# QUTMS-TSAL-V00-S00.net
KiCad netlist of a schematic drawn in Altium Designer
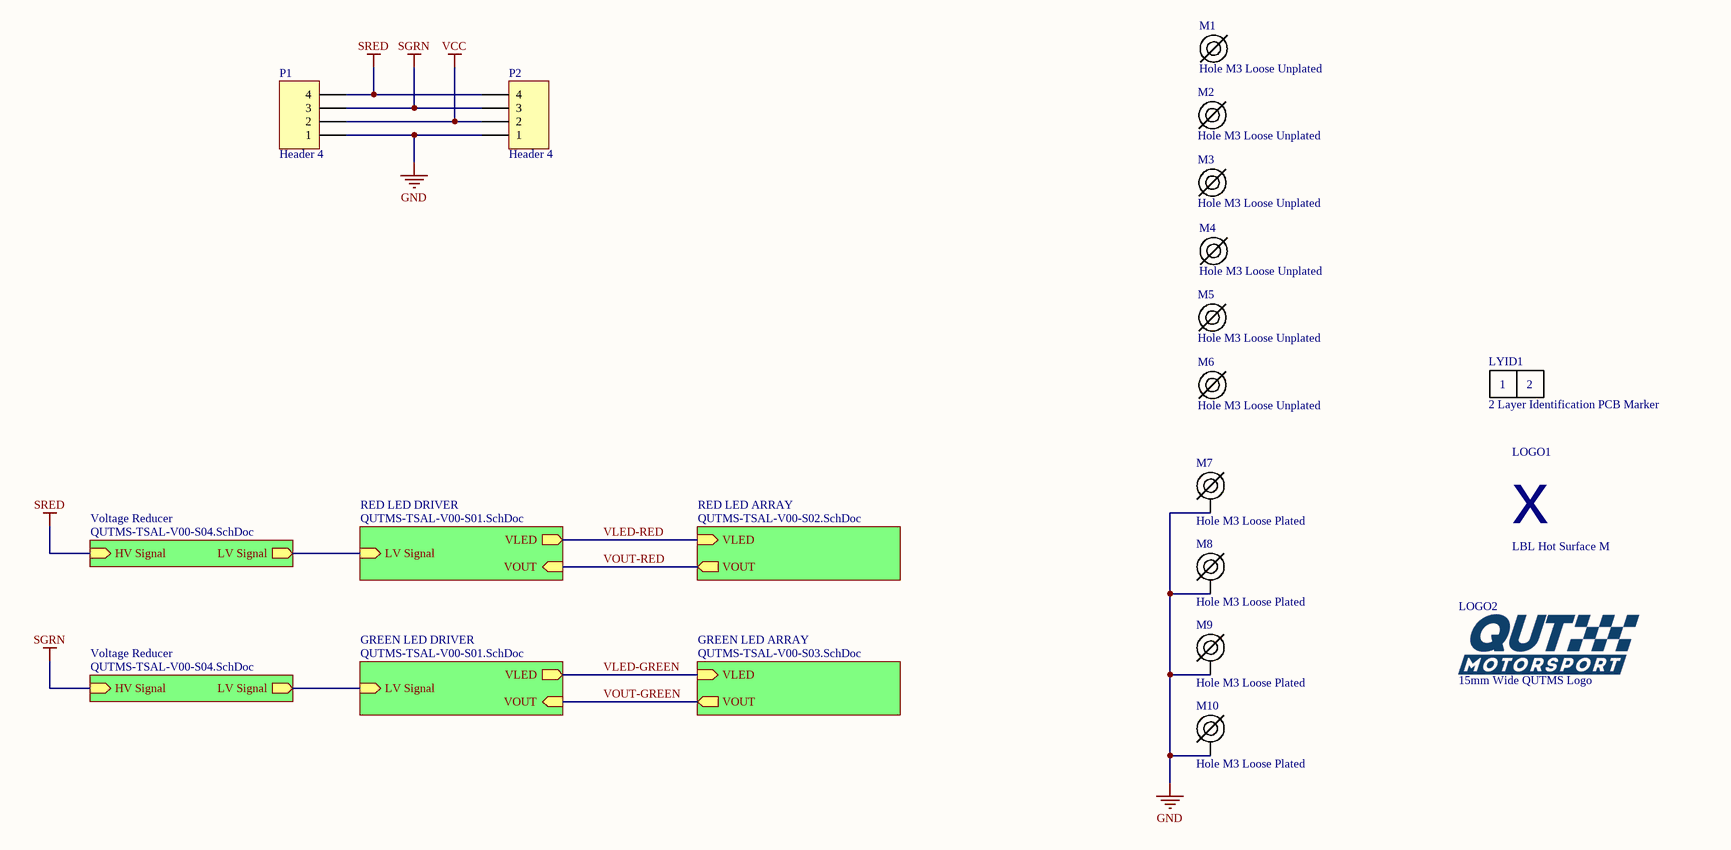
[diagram p0: QUTMS-TSAL-V00-S00.SchDoc]

(export (version "E")
  (design (tool "Eeschema 10.0.6"))
  (components
    (comp (ref "LOGO1")
      (value "LBL Hot Surface M")
      (footprint "LBL HOT MEDIUM")
      (libsource (lib "QUTMS_PCBLibrary") (part "LBL Hot Surface M"))
    )
    (comp (ref "LOGO2")
      (value "15mm Wide QUTMS Logo")
      (footprint "QUTMS LOGO 15MM")
      (libsource (lib "QUTMS_PCBLibrary") (part "QUTMS Logo 15mm"))
    )
    (comp (ref "LYID1")
      (value "2 Layer Identification PCB Marker")
      (footprint "LAYER IDENT 2")
      (libsource (lib "QUTMS_PCBLibrary") (part "Layer Identification 2"))
    )
    (comp (ref "M1")
      (value "Hole M3 Loose Unplated")
      (footprint "M3.5 UNPLATED")
      (description "M3.5 Hole, No Plating")
      (libsource (lib "QUTMS_PCBLibrary") (part "Hole M3 Loose Unplated"))
    )
    (comp (ref "M2")
      (value "Hole M3 Loose Unplated")
      (footprint "M3.5 UNPLATED")
      (description "M3.5 Hole, No Plating")
      (libsource (lib "QUTMS_PCBLibrary") (part "Hole M3 Loose Unplated"))
    )
    (comp (ref "M3")
      (value "Hole M3 Loose Unplated")
      (footprint "M3.5 UNPLATED")
      (description "M3.5 Hole, No Plating")
      (libsource (lib "QUTMS_PCBLibrary") (part "Hole M3 Loose Unplated"))
    )
    (comp (ref "M4")
      (value "Hole M3 Loose Unplated")
      (footprint "M3.5 UNPLATED")
      (description "M3.5 Hole, No Plating")
      (libsource (lib "QUTMS_PCBLibrary") (part "Hole M3 Loose Unplated"))
    )
    (comp (ref "M5")
      (value "Hole M3 Loose Unplated")
      (footprint "M3.5 UNPLATED")
      (description "M3.5 Hole, No Plating")
      (libsource (lib "QUTMS_PCBLibrary") (part "Hole M3 Loose Unplated"))
    )
    (comp (ref "M6")
      (value "Hole M3 Loose Unplated")
      (footprint "M3.5 UNPLATED")
      (description "M3.5 Hole, No Plating")
      (libsource (lib "QUTMS_PCBLibrary") (part "Hole M3 Loose Unplated"))
    )
    (comp (ref "M7")
      (value "Hole M3 Loose Plated")
      (footprint "M3.5 PLATED")
      (description "M3.5 Hole, Plated")
      (libsource (lib "QUTMS_PCBLibrary") (part "Hole M3 Loose Plated"))
    )
    (comp (ref "M8")
      (value "Hole M3 Loose Plated")
      (footprint "M3.5 PLATED")
      (description "M3.5 Hole, Plated")
      (libsource (lib "QUTMS_PCBLibrary") (part "Hole M3 Loose Plated"))
    )
    (comp (ref "M9")
      (value "Hole M3 Loose Plated")
      (footprint "M3.5 PLATED")
      (description "M3.5 Hole, Plated")
      (libsource (lib "QUTMS_PCBLibrary") (part "Hole M3 Loose Plated"))
    )
    (comp (ref "M10")
      (value "Hole M3 Loose Plated")
      (footprint "M3.5 PLATED")
      (description "M3.5 Hole, Plated")
      (libsource (lib "QUTMS_PCBLibrary") (part "Hole M3 Loose Plated"))
    )
    (comp (ref "P1")
      (value "Header 4")
      (footprint "HDR1X4")
      (description "Header, 4-Pin")
      (fields (field (name "PUBLISHER") "Altium Limited"))
      (libsource (lib "") (part "Header 4_1"))
    )
    (comp (ref "P2")
      (value "Header 4")
      (footprint "HDR1X4")
      (description "Header, 4-Pin")
      (fields (field (name "PUBLISHER") "Altium Limited"))
      (libsource (lib "Miscellaneous Connectors") (part "Header 4"))
    )
  )
  (nets
    (net (code "7") (name "GND") (class "Default")
      (node (ref "M10") (pin "1") (pinfunction "1_1") (pintype "passive"))
      (node (ref "M7") (pin "1") (pinfunction "1_1") (pintype "passive"))
      (node (ref "M8") (pin "1") (pinfunction "1_1") (pintype "passive"))
      (node (ref "M9") (pin "1") (pinfunction "1_1") (pintype "passive"))
      (node (ref "P1") (pin "1") (pinfunction "1_1") (pintype "passive"))
      (node (ref "P2") (pin "1") (pinfunction "1_1") (pintype "passive"))
    )
    (net (code "8") (name "SGRN") (class "Default")
      (node (ref "P1") (pin "3") (pinfunction "3_3") (pintype "passive"))
      (node (ref "P2") (pin "3") (pinfunction "3_3") (pintype "passive"))
    )
    (net (code "9") (name "SRED") (class "Default")
      (node (ref "P1") (pin "4") (pinfunction "4_4") (pintype "passive"))
      (node (ref "P2") (pin "4") (pinfunction "4_4") (pintype "passive"))
    )
    (net (code "10") (name "VCC") (class "Default")
      (node (ref "P1") (pin "2") (pinfunction "2_2") (pintype "passive"))
      (node (ref "P2") (pin "2") (pinfunction "2_2") (pintype "passive"))
    )
  )
)
